# shrew-mega.net
KiCad netlist of a schematic drawn in EAGLE
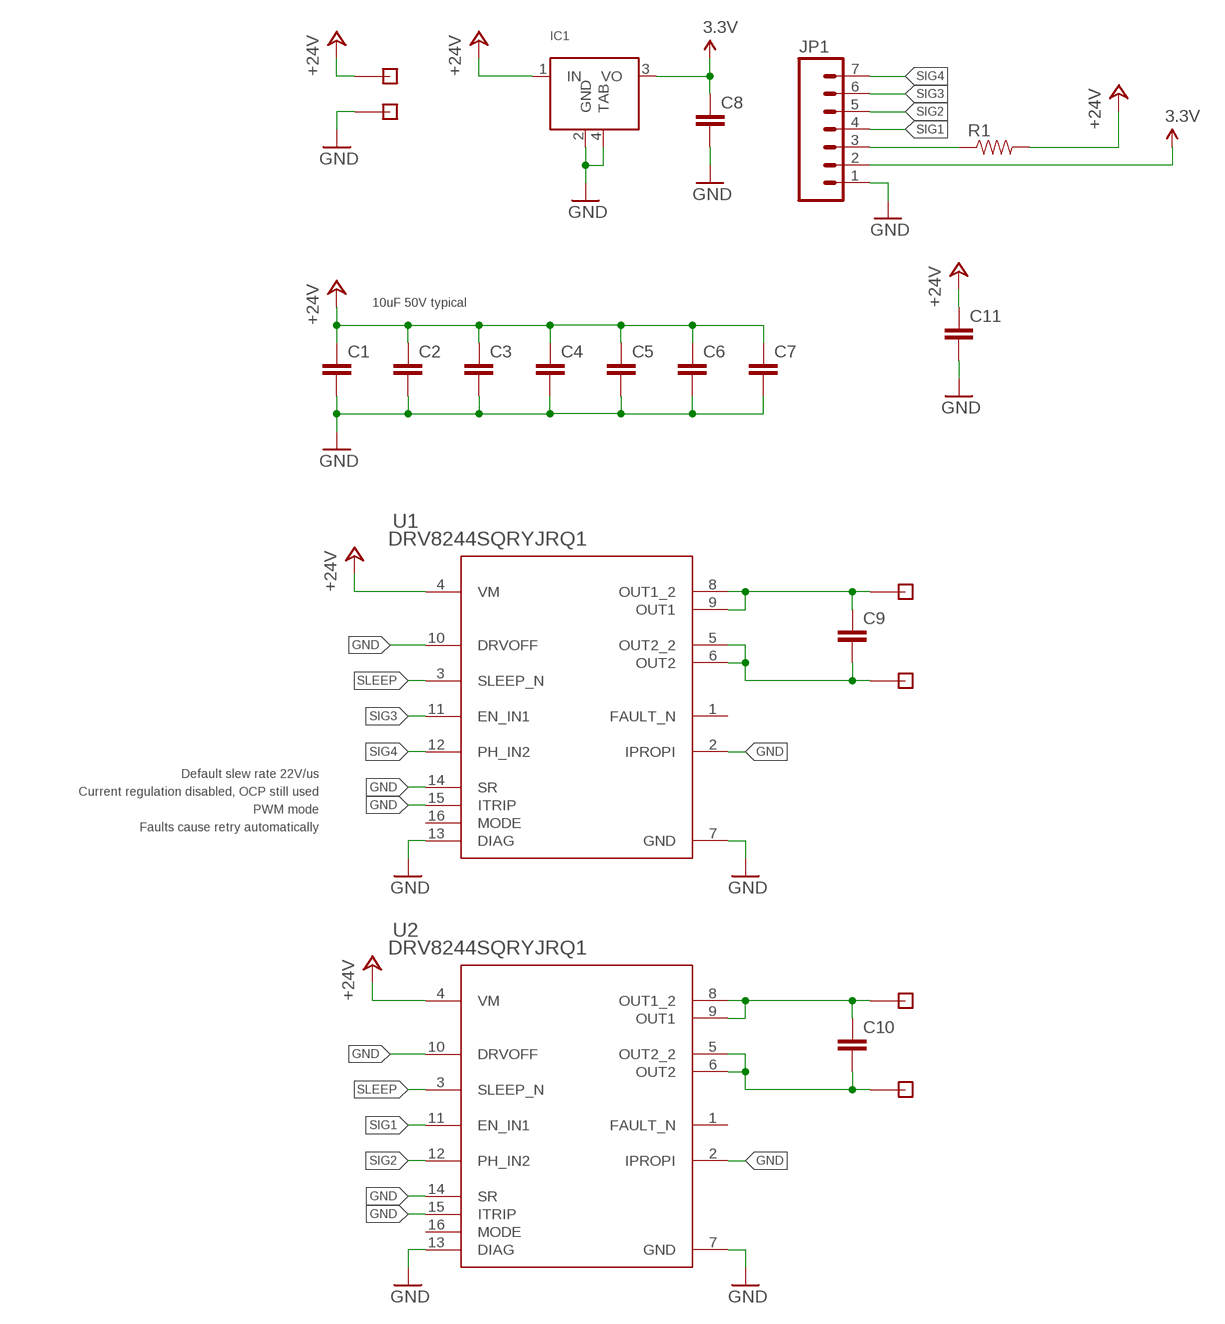
[diagram p0: schematic, sheet 1]

(export (version "E")
  (design (tool "Eeschema 10.0.6"))
  (components
    (comp (ref "C1")
      (value "CAP0805")
      (footprint "eagle-import:0805")
      (libsource (lib "eagle-import") (part "CAP0805"))
    )
    (comp (ref "C2")
      (value "CAP0805")
      (footprint "eagle-import:0805")
      (libsource (lib "eagle-import") (part "CAP0805"))
    )
    (comp (ref "C3")
      (value "CAP0805")
      (footprint "eagle-import:0805")
      (libsource (lib "eagle-import") (part "CAP0805"))
    )
    (comp (ref "C4")
      (value "CAP0805")
      (footprint "eagle-import:0805")
      (libsource (lib "eagle-import") (part "CAP0805"))
    )
    (comp (ref "C5")
      (value "CAP0805")
      (footprint "eagle-import:0805")
      (libsource (lib "eagle-import") (part "CAP0805"))
    )
    (comp (ref "C6")
      (value "CAP0805")
      (footprint "eagle-import:0805")
      (libsource (lib "eagle-import") (part "CAP0805"))
    )
    (comp (ref "C7")
      (value "CAP0805")
      (footprint "eagle-import:0805")
      (libsource (lib "eagle-import") (part "CAP0805"))
    )
    (comp (ref "C8")
      (value "CAP0805")
      (footprint "eagle-import:0805")
      (libsource (lib "eagle-import") (part "CAP0805"))
    )
    (comp (ref "C9")
      (value "CAP0402-CAP")
      (footprint "eagle-import:0402-CAP")
      (libsource (lib "eagle-import") (part "CAP0402-CAP"))
    )
    (comp (ref "C10")
      (value "CAP0402-CAP")
      (footprint "eagle-import:0402-CAP")
      (libsource (lib "eagle-import") (part "CAP0402-CAP"))
    )
    (comp (ref "C11")
      (value "CAP0805")
      (footprint "eagle-import:0805")
      (libsource (lib "eagle-import") (part "CAP0805"))
    )
    (comp (ref "IC1")
      (value "V_REG_SOT-SOT223")
      (footprint "eagle-import:SOT223")
      (libsource (lib "eagle-import") (part "V_REG_SOT-SOT223"))
    )
    (comp (ref "JP1")
      (value "M07-2MM-TH")
      (footprint "eagle-import:1X07-2MM-TH")
      (libsource (lib "eagle-import") (part "M07-2MM-TH"))
    )
    (comp (ref "R1")
      (value "RESISTOR0402-RES")
      (footprint "eagle-import:0402-RES")
      (libsource (lib "eagle-import") (part "RESISTOR0402-RES"))
    )
    (comp (ref "U1")
      (value "DRV8244SQRYJRQ1")
      (footprint "eagle-import:RYJ0016A-MFG")
      (fields (field (name "COPYRIGHT") "Copyright (C) 2024 Ultra Librarian. All rights reserved."))
      (libsource (lib "eagle-import") (part "DRV8244SQRYJRQ1"))
    )
    (comp (ref "U2")
      (value "DRV8244SQRYJRQ1")
      (footprint "eagle-import:RYJ0016A-MFG")
      (fields (field (name "COPYRIGHT") "Copyright (C) 2024 Ultra Librarian. All rights reserved."))
      (libsource (lib "eagle-import") (part "DRV8244SQRYJRQ1"))
    )
    (comp (ref "X1")
      (value "PIN-1X-BIG")
      (footprint "eagle-import:PAD-1X-BIG")
      (libsource (lib "eagle-import") (part "PIN-1X-BIG"))
    )
    (comp (ref "X2")
      (value "PIN-1X-BIG")
      (footprint "eagle-import:PAD-1X-BIG")
      (libsource (lib "eagle-import") (part "PIN-1X-BIG"))
    )
    (comp (ref "X3")
      (value "PIN-1X-BIG")
      (footprint "eagle-import:PAD-1X-BIG")
      (libsource (lib "eagle-import") (part "PIN-1X-BIG"))
    )
    (comp (ref "X4")
      (value "PIN-1X-BIG")
      (footprint "eagle-import:PAD-1X-BIG")
      (libsource (lib "eagle-import") (part "PIN-1X-BIG"))
    )
    (comp (ref "X5")
      (value "PIN-1X-BIG")
      (footprint "eagle-import:PAD-1X-BIG")
      (libsource (lib "eagle-import") (part "PIN-1X-BIG"))
    )
    (comp (ref "X6")
      (value "PIN-1X-BIG")
      (footprint "eagle-import:PAD-1X-BIG")
      (libsource (lib "eagle-import") (part "PIN-1X-BIG"))
    )
  )
  (nets
    (net (code "1") (name "+24V") (class "Default")
      (node (ref "C1") (pin "1") (pinfunction "1_1") (pintype "passive"))
      (node (ref "C11") (pin "1") (pinfunction "1_1") (pintype "passive"))
      (node (ref "C2") (pin "1") (pinfunction "1_1") (pintype "passive"))
      (node (ref "C3") (pin "1") (pinfunction "1_1") (pintype "passive"))
      (node (ref "C4") (pin "1") (pinfunction "1_1") (pintype "passive"))
      (node (ref "C5") (pin "1") (pinfunction "1_1") (pintype "passive"))
      (node (ref "C6") (pin "1") (pinfunction "1_1") (pintype "passive"))
      (node (ref "C7") (pin "1") (pinfunction "1_1") (pintype "passive"))
      (node (ref "IC1") (pin "1") (pinfunction "IN_1") (pintype "input"))
      (node (ref "R1") (pin "2") (pinfunction "2_2") (pintype "passive"))
      (node (ref "U1") (pin "4") (pinfunction "VM_4") (pintype "input"))
      (node (ref "U2") (pin "4") (pinfunction "VM_4") (pintype "input"))
      (node (ref "X5") (pin "1") (pinfunction "P$1_1") (pintype "bidirectional"))
    )
    (net (code "2") (name "3.3V") (class "Default")
      (node (ref "C8") (pin "1") (pinfunction "1_1") (pintype "passive"))
      (node (ref "IC1") (pin "3") (pinfunction "VO_3") (pintype "output"))
      (node (ref "JP1") (pin "2") (pinfunction "2_2") (pintype "passive"))
    )
    (net (code "3") (name "GND") (class "Default")
      (node (ref "C1") (pin "2") (pinfunction "2_2") (pintype "passive"))
      (node (ref "C11") (pin "2") (pinfunction "2_2") (pintype "passive"))
      (node (ref "C2") (pin "2") (pinfunction "2_2") (pintype "passive"))
      (node (ref "C3") (pin "2") (pinfunction "2_2") (pintype "passive"))
      (node (ref "C4") (pin "2") (pinfunction "2_2") (pintype "passive"))
      (node (ref "C5") (pin "2") (pinfunction "2_2") (pintype "passive"))
      (node (ref "C6") (pin "2") (pinfunction "2_2") (pintype "passive"))
      (node (ref "C7") (pin "2") (pinfunction "2_2") (pintype "passive"))
      (node (ref "C8") (pin "2") (pinfunction "2_2") (pintype "passive"))
      (node (ref "IC1") (pin "2") (pinfunction "GND_2") (pintype "input"))
      (node (ref "IC1") (pin "4") (pinfunction "TAB_4") (pintype "input"))
      (node (ref "JP1") (pin "1") (pinfunction "1_1") (pintype "passive"))
      (node (ref "U1") (pin "10") (pinfunction "DRVOFF_10") (pintype "input"))
      (node (ref "U1") (pin "13") (pinfunction "DIAG_13") (pintype "passive"))
      (node (ref "U1") (pin "14") (pinfunction "SR_14") (pintype "passive"))
      (node (ref "U1") (pin "15") (pinfunction "ITRIP_15") (pintype "passive"))
      (node (ref "U1") (pin "2") (pinfunction "IPROPI_2") (pintype "passive"))
      (node (ref "U1") (pin "7") (pinfunction "GND_7") (pintype "input"))
      (node (ref "U2") (pin "10") (pinfunction "DRVOFF_10") (pintype "input"))
      (node (ref "U2") (pin "13") (pinfunction "DIAG_13") (pintype "passive"))
      (node (ref "U2") (pin "14") (pinfunction "SR_14") (pintype "passive"))
      (node (ref "U2") (pin "15") (pinfunction "ITRIP_15") (pintype "passive"))
      (node (ref "U2") (pin "2") (pinfunction "IPROPI_2") (pintype "passive"))
      (node (ref "U2") (pin "7") (pinfunction "GND_7") (pintype "input"))
      (node (ref "X6") (pin "1") (pinfunction "P$1_1") (pintype "bidirectional"))
    )
    (net (code "4") (name "Net-(JP1-Pad3)") (class "Default")
      (node (ref "JP1") (pin "3") (pinfunction "3_3") (pintype "passive"))
      (node (ref "R1") (pin "1") (pinfunction "1_1") (pintype "passive"))
    )
    (net (code "5") (name "Net-(U1-OUT1)") (class "Default")
      (node (ref "C9") (pin "1") (pinfunction "1_1") (pintype "passive"))
      (node (ref "U1") (pin "8") (pinfunction "OUT1_2_8") (pintype "output"))
      (node (ref "U1") (pin "9") (pinfunction "OUT1_9") (pintype "output"))
      (node (ref "X2") (pin "1") (pinfunction "P$1_1") (pintype "bidirectional"))
    )
    (net (code "6") (name "Net-(U1-OUT2)") (class "Default")
      (node (ref "C9") (pin "2") (pinfunction "2_2") (pintype "passive"))
      (node (ref "U1") (pin "5") (pinfunction "OUT2_2_5") (pintype "output"))
      (node (ref "U1") (pin "6") (pinfunction "OUT2_6") (pintype "output"))
      (node (ref "X1") (pin "1") (pinfunction "P$1_1") (pintype "bidirectional"))
    )
    (net (code "7") (name "Net-(U2-OUT1)") (class "Default")
      (node (ref "C10") (pin "1") (pinfunction "1_1") (pintype "passive"))
      (node (ref "U2") (pin "8") (pinfunction "OUT1_2_8") (pintype "output"))
      (node (ref "U2") (pin "9") (pinfunction "OUT1_9") (pintype "output"))
      (node (ref "X4") (pin "1") (pinfunction "P$1_1") (pintype "bidirectional"))
    )
    (net (code "8") (name "Net-(U2-OUT2)") (class "Default")
      (node (ref "C10") (pin "2") (pinfunction "2_2") (pintype "passive"))
      (node (ref "U2") (pin "5") (pinfunction "OUT2_2_5") (pintype "output"))
      (node (ref "U2") (pin "6") (pinfunction "OUT2_6") (pintype "output"))
      (node (ref "X3") (pin "1") (pinfunction "P$1_1") (pintype "bidirectional"))
    )
    (net (code "9") (name "SIG1") (class "Default")
      (node (ref "JP1") (pin "4") (pinfunction "4_4") (pintype "passive"))
      (node (ref "U2") (pin "11") (pinfunction "EN_IN1_11") (pintype "input"))
    )
    (net (code "10") (name "SIG2") (class "Default")
      (node (ref "JP1") (pin "5") (pinfunction "5_5") (pintype "passive"))
      (node (ref "U2") (pin "12") (pinfunction "PH_IN2_12") (pintype "input"))
    )
    (net (code "11") (name "SIG3") (class "Default")
      (node (ref "JP1") (pin "6") (pinfunction "6_6") (pintype "passive"))
      (node (ref "U1") (pin "11") (pinfunction "EN_IN1_11") (pintype "input"))
    )
    (net (code "12") (name "SIG4") (class "Default")
      (node (ref "JP1") (pin "7") (pinfunction "7_7") (pintype "passive"))
      (node (ref "U1") (pin "12") (pinfunction "PH_IN2_12") (pintype "input"))
    )
    (net (code "13") (name "SLEEP") (class "Default")
      (node (ref "U1") (pin "3") (pinfunction "SLEEP_N_3") (pintype "input"))
      (node (ref "U2") (pin "3") (pinfunction "SLEEP_N_3") (pintype "input"))
    )
    (net (code "14") (name "unconnected-(U1-FAULT_N-Pad1)") (class "Default")
      (node (ref "U1") (pin "1") (pinfunction "FAULT_N_1") (pintype "open_collector"))
    )
    (net (code "15") (name "unconnected-(U1-MODE-Pad16)") (class "Default")
      (node (ref "U1") (pin "16") (pinfunction "MODE_16") (pintype "passive"))
    )
    (net (code "16") (name "unconnected-(U2-FAULT_N-Pad1)") (class "Default")
      (node (ref "U2") (pin "1") (pinfunction "FAULT_N_1") (pintype "open_collector"))
    )
    (net (code "17") (name "unconnected-(U2-MODE-Pad16)") (class "Default")
      (node (ref "U2") (pin "16") (pinfunction "MODE_16") (pintype "passive"))
    )
  )
)
